# 03-MEMORY.net
KiCad netlist of a schematic drawn in Altium Designer
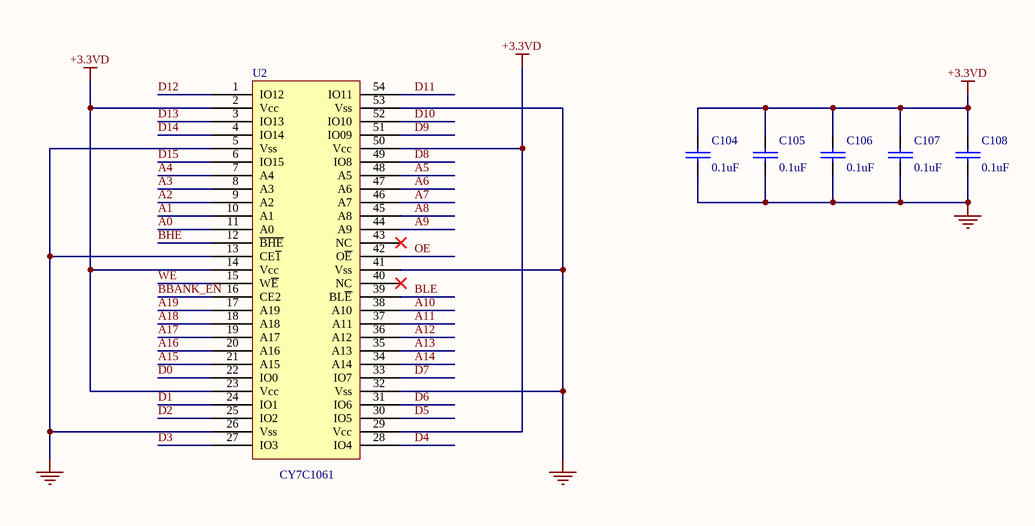
[diagram p0: 03-MEMORY.SchDoc]

(export (version "E")
  (design (tool "Eeschema 10.0.6"))
  (components
    (comp (ref "C104")
      (value "0.1uF")
      (footprint "0603")
      (description "Capacitor")
      (libsource (lib "*") (part "CAP"))
    )
    (comp (ref "C105")
      (value "0.1uF")
      (footprint "0603")
      (description "Capacitor")
      (libsource (lib "*") (part "CAP"))
    )
    (comp (ref "C106")
      (value "0.1uF")
      (footprint "0603")
      (description "Capacitor")
      (libsource (lib "*") (part "CAP"))
    )
    (comp (ref "C107")
      (value "0.1uF")
      (footprint "0603")
      (description "Capacitor")
      (libsource (lib "*") (part "CAP"))
    )
    (comp (ref "C108")
      (value "0.1uF")
      (footprint "0603")
      (description "Capacitor")
      (libsource (lib "*") (part "CAP"))
    )
    (comp (ref "U2")
      (value "CY7C1061")
      (footprint "TSOP54")
      (description "CY7C1061AC")
      (libsource (lib "*") (part "CY7C1061"))
    )
  )
  (nets
    (net (code "1") (name "+3.3VD") (class "Default")
      (node (ref "C104") (pin "1") (pinfunction "1_1") (pintype "passive"))
      (node (ref "C105") (pin "1") (pinfunction "1_1") (pintype "passive"))
      (node (ref "C106") (pin "1") (pinfunction "1_1") (pintype "passive"))
      (node (ref "C107") (pin "1") (pinfunction "1_1") (pintype "passive"))
      (node (ref "C108") (pin "1") (pinfunction "1_1") (pintype "passive"))
      (node (ref "U2") (pin "14") (pinfunction "Vcc_14") (pintype "passive"))
      (node (ref "U2") (pin "2") (pinfunction "Vcc_2") (pintype "passive"))
      (node (ref "U2") (pin "23") (pinfunction "Vcc_23") (pintype "passive"))
      (node (ref "U2") (pin "29") (pinfunction "Vcc_29") (pintype "passive"))
      (node (ref "U2") (pin "50") (pinfunction "Vcc_50") (pintype "passive"))
    )
    (net (code "2") (name "/A0") (class "Default")
      (node (ref "U2") (pin "11") (pinfunction "A0_11") (pintype "passive"))
    )
    (net (code "3") (name "/A1") (class "Default")
      (node (ref "U2") (pin "10") (pinfunction "A1_10") (pintype "passive"))
    )
    (net (code "4") (name "/A2") (class "Default")
      (node (ref "U2") (pin "9") (pinfunction "A2_9") (pintype "passive"))
    )
    (net (code "5") (name "/A3") (class "Default")
      (node (ref "U2") (pin "8") (pinfunction "A3_8") (pintype "passive"))
    )
    (net (code "6") (name "/A4") (class "Default")
      (node (ref "U2") (pin "7") (pinfunction "A4_7") (pintype "passive"))
    )
    (net (code "7") (name "/A5") (class "Default")
      (node (ref "U2") (pin "48") (pinfunction "A5_48") (pintype "passive"))
    )
    (net (code "8") (name "/A6") (class "Default")
      (node (ref "U2") (pin "47") (pinfunction "A6_47") (pintype "passive"))
    )
    (net (code "9") (name "/A7") (class "Default")
      (node (ref "U2") (pin "46") (pinfunction "A7_46") (pintype "passive"))
    )
    (net (code "10") (name "/A8") (class "Default")
      (node (ref "U2") (pin "45") (pinfunction "A8_45") (pintype "passive"))
    )
    (net (code "11") (name "/A9") (class "Default")
      (node (ref "U2") (pin "44") (pinfunction "A9_44") (pintype "passive"))
    )
    (net (code "12") (name "/A10") (class "Default")
      (node (ref "U2") (pin "38") (pinfunction "A10_38") (pintype "passive"))
    )
    (net (code "13") (name "/A11") (class "Default")
      (node (ref "U2") (pin "37") (pinfunction "A11_37") (pintype "passive"))
    )
    (net (code "14") (name "/A12") (class "Default")
      (node (ref "U2") (pin "36") (pinfunction "A12_36") (pintype "passive"))
    )
    (net (code "15") (name "/A13") (class "Default")
      (node (ref "U2") (pin "35") (pinfunction "A13_35") (pintype "passive"))
    )
    (net (code "16") (name "/A14") (class "Default")
      (node (ref "U2") (pin "34") (pinfunction "A14_34") (pintype "passive"))
    )
    (net (code "17") (name "/A15") (class "Default")
      (node (ref "U2") (pin "21") (pinfunction "A15_21") (pintype "passive"))
    )
    (net (code "18") (name "/A16") (class "Default")
      (node (ref "U2") (pin "20") (pinfunction "A16_20") (pintype "passive"))
    )
    (net (code "19") (name "/A17") (class "Default")
      (node (ref "U2") (pin "19") (pinfunction "A17_19") (pintype "passive"))
    )
    (net (code "20") (name "/A18") (class "Default")
      (node (ref "U2") (pin "18") (pinfunction "A18_18") (pintype "passive"))
    )
    (net (code "21") (name "/A19") (class "Default")
      (node (ref "U2") (pin "17") (pinfunction "A19_17") (pintype "passive"))
    )
    (net (code "22") (name "/BBANK_EN") (class "Default")
      (node (ref "U2") (pin "16") (pinfunction "CE2_16") (pintype "passive"))
    )
    (net (code "23") (name "/BHE") (class "Default")
      (node (ref "U2") (pin "12") (pinfunction "~{BHE}_12") (pintype "passive"))
    )
    (net (code "24") (name "/BLE") (class "Default")
      (node (ref "U2") (pin "39") (pinfunction "BL~{E}_39") (pintype "passive"))
    )
    (net (code "25") (name "/D0") (class "Default")
      (node (ref "U2") (pin "22") (pinfunction "IO0_22") (pintype "passive"))
    )
    (net (code "26") (name "/D1") (class "Default")
      (node (ref "U2") (pin "24") (pinfunction "IO1_24") (pintype "passive"))
    )
    (net (code "27") (name "/D2") (class "Default")
      (node (ref "U2") (pin "25") (pinfunction "IO2_25") (pintype "passive"))
    )
    (net (code "28") (name "/D3") (class "Default")
      (node (ref "U2") (pin "27") (pinfunction "IO3_27") (pintype "passive"))
    )
    (net (code "29") (name "/D4") (class "Default")
      (node (ref "U2") (pin "28") (pinfunction "IO4_28") (pintype "passive"))
    )
    (net (code "30") (name "/D5") (class "Default")
      (node (ref "U2") (pin "30") (pinfunction "IO5_30") (pintype "passive"))
    )
    (net (code "31") (name "/D6") (class "Default")
      (node (ref "U2") (pin "31") (pinfunction "IO6_31") (pintype "passive"))
    )
    (net (code "32") (name "/D7") (class "Default")
      (node (ref "U2") (pin "33") (pinfunction "IO7_33") (pintype "passive"))
    )
    (net (code "33") (name "/D8") (class "Default")
      (node (ref "U2") (pin "49") (pinfunction "IO8_49") (pintype "passive"))
    )
    (net (code "34") (name "/D9") (class "Default")
      (node (ref "U2") (pin "51") (pinfunction "IO09_51") (pintype "passive"))
    )
    (net (code "35") (name "/D10") (class "Default")
      (node (ref "U2") (pin "52") (pinfunction "IO10_52") (pintype "passive"))
    )
    (net (code "36") (name "/D11") (class "Default")
      (node (ref "U2") (pin "54") (pinfunction "IO11_54") (pintype "passive"))
    )
    (net (code "37") (name "/D12") (class "Default")
      (node (ref "U2") (pin "1") (pinfunction "IO12_1") (pintype "passive"))
    )
    (net (code "38") (name "/D13") (class "Default")
      (node (ref "U2") (pin "3") (pinfunction "IO13_3") (pintype "passive"))
    )
    (net (code "39") (name "/D14") (class "Default")
      (node (ref "U2") (pin "4") (pinfunction "IO14_4") (pintype "passive"))
    )
    (net (code "40") (name "/D15") (class "Default")
      (node (ref "U2") (pin "6") (pinfunction "IO15_6") (pintype "passive"))
    )
    (net (code "41") (name "/OE") (class "Default")
      (node (ref "U2") (pin "42") (pinfunction "O~{E}_42") (pintype "passive"))
    )
    (net (code "42") (name "/WE") (class "Default")
      (node (ref "U2") (pin "15") (pinfunction "W~{E}_15") (pintype "passive"))
    )
    (net (code "43") (name "DGND") (class "Default")
      (node (ref "C104") (pin "2") (pinfunction "2_2") (pintype "passive"))
      (node (ref "C105") (pin "2") (pinfunction "2_2") (pintype "passive"))
      (node (ref "C106") (pin "2") (pinfunction "2_2") (pintype "passive"))
      (node (ref "C107") (pin "2") (pinfunction "2_2") (pintype "passive"))
      (node (ref "C108") (pin "2") (pinfunction "2_2") (pintype "passive"))
      (node (ref "U2") (pin "13") (pinfunction "CE~{1}_13") (pintype "passive"))
      (node (ref "U2") (pin "26") (pinfunction "Vss_26") (pintype "passive"))
      (node (ref "U2") (pin "32") (pinfunction "Vss_32") (pintype "passive"))
      (node (ref "U2") (pin "41") (pinfunction "Vss_41") (pintype "passive"))
      (node (ref "U2") (pin "5") (pinfunction "Vss_5") (pintype "passive"))
      (node (ref "U2") (pin "53") (pinfunction "Vss_53") (pintype "passive"))
    )
    (net (code "44") (name "unconnected-(U2-NC-Pad40)") (class "Default")
      (node (ref "U2") (pin "40") (pinfunction "NC_40") (pintype "passive+no_connect"))
    )
    (net (code "45") (name "unconnected-(U2-NC-Pad43)") (class "Default")
      (node (ref "U2") (pin "43") (pinfunction "NC_43") (pintype "passive+no_connect"))
    )
  )
)
